# IO-Expander.net
KiCad netlist of a schematic drawn in Altium Designer
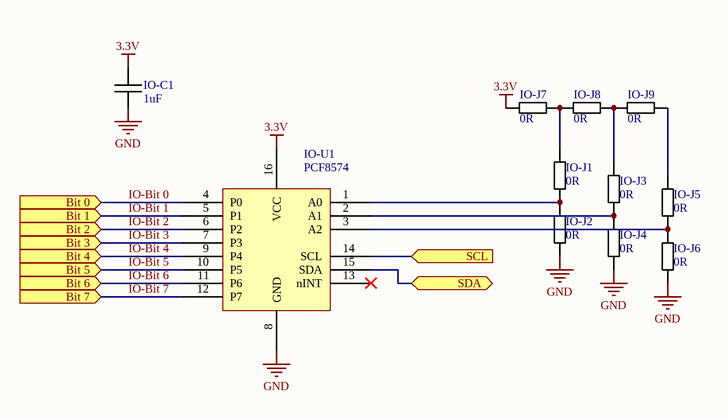
[diagram p0: IO-Expander.SchDoc]

(export (version "E")
  (design (tool "Eeschema 10.0.6"))
  (components
    (comp (ref "IO-C1")
      (value "1uF")
      (footprint "C 0805 / 2012")
      (libsource (lib "Standard") (part "Capacitor"))
    )
    (comp (ref "IO-J1") (value "0R") (footprint "R 0805 / 2012") (libsource (lib "") (part "Resistor_1")))
    (comp (ref "IO-J2") (value "0R") (footprint "R 0805 / 2012") (libsource (lib "") (part "Resistor_1")))
    (comp (ref "IO-J3") (value "0R") (footprint "R 0805 / 2012") (libsource (lib "") (part "Resistor_1")))
    (comp (ref "IO-J4") (value "0R") (footprint "R 0805 / 2012") (libsource (lib "") (part "Resistor_1")))
    (comp (ref "IO-J5") (value "0R") (footprint "R 0805 / 2012") (libsource (lib "") (part "Resistor_1")))
    (comp (ref "IO-J6") (value "0R") (footprint "R 0805 / 2012") (libsource (lib "") (part "Resistor_1")))
    (comp (ref "IO-J7")
      (value "0R")
      (footprint "R 0805 / 2012 wide")
      (libsource (lib "Standard") (part "Resistor"))
    )
    (comp (ref "IO-J8")
      (value "0R")
      (footprint "R 0805 / 2012 wide")
      (libsource (lib "Standard") (part "Resistor"))
    )
    (comp (ref "IO-J9")
      (value "0R")
      (footprint "R 0805 / 2012 wide")
      (libsource (lib "Standard") (part "Resistor"))
    )
    (comp (ref "IO-U1")
      (value "PCF8574")
      (footprint "SOIC-16W")
      (description "8-Bit I/O-Expander")
      (libsource (lib "ICs") (part "PCF8574"))
    )
  )
  (nets
    (net (code "1") (name "/IO-Bit 0") (class "Default")
      (node (ref "IO-U1") (pin "4") (pinfunction "P0_4") (pintype "passive"))
    )
    (net (code "2") (name "/IO-Bit 1") (class "Default")
      (node (ref "IO-U1") (pin "5") (pinfunction "P1_5") (pintype "passive"))
    )
    (net (code "3") (name "/IO-Bit 2") (class "Default")
      (node (ref "IO-U1") (pin "6") (pinfunction "P2_6") (pintype "passive"))
    )
    (net (code "4") (name "/IO-Bit 3") (class "Default")
      (node (ref "IO-U1") (pin "7") (pinfunction "P3_7") (pintype "passive"))
    )
    (net (code "5") (name "/IO-Bit 4") (class "Default")
      (node (ref "IO-U1") (pin "9") (pinfunction "P4_9") (pintype "passive"))
    )
    (net (code "6") (name "/IO-Bit 5") (class "Default")
      (node (ref "IO-U1") (pin "10") (pinfunction "P5_10") (pintype "passive"))
    )
    (net (code "7") (name "/IO-Bit 6") (class "Default")
      (node (ref "IO-U1") (pin "11") (pinfunction "P6_11") (pintype "passive"))
    )
    (net (code "8") (name "/IO-Bit 7") (class "Default")
      (node (ref "IO-U1") (pin "12") (pinfunction "P7_12") (pintype "passive"))
    )
    (net (code "9") (name "/SCL") (class "Default")
      (node (ref "IO-U1") (pin "14") (pinfunction "SCL_14") (pintype "passive"))
    )
    (net (code "10") (name "/SDA") (class "Default")
      (node (ref "IO-U1") (pin "15") (pinfunction "SDA_15") (pintype "passive"))
    )
    (net (code "11") (name "3.3V") (class "Default")
      (node (ref "IO-C1") (pin "1") (pinfunction "1_1") (pintype "passive"))
      (node (ref "IO-J7") (pin "2") (pinfunction "2_2") (pintype "passive"))
      (node (ref "IO-U1") (pin "16") (pinfunction "VCC_16") (pintype "passive"))
    )
    (net (code "12") (name "GND") (class "Default")
      (node (ref "IO-C1") (pin "2") (pinfunction "1_2") (pintype "passive"))
      (node (ref "IO-J2") (pin "1") (pinfunction "1_1") (pintype "passive"))
      (node (ref "IO-J4") (pin "1") (pinfunction "1_1") (pintype "passive"))
      (node (ref "IO-J6") (pin "1") (pinfunction "1_1") (pintype "passive"))
      (node (ref "IO-U1") (pin "8") (pinfunction "GND_8") (pintype "passive"))
    )
    (net (code "13") (name "Net-(IO-J1-Pad2)") (class "Default")
      (node (ref "IO-J1") (pin "2") (pinfunction "2_2") (pintype "passive"))
      (node (ref "IO-J7") (pin "1") (pinfunction "1_1") (pintype "passive"))
      (node (ref "IO-J8") (pin "2") (pinfunction "2_2") (pintype "passive"))
    )
    (net (code "14") (name "Net-(IO-J3-Pad2)") (class "Default")
      (node (ref "IO-J3") (pin "2") (pinfunction "2_2") (pintype "passive"))
      (node (ref "IO-J8") (pin "1") (pinfunction "1_1") (pintype "passive"))
      (node (ref "IO-J9") (pin "2") (pinfunction "2_2") (pintype "passive"))
    )
    (net (code "15") (name "Net-(IO-J5-Pad2)") (class "Default")
      (node (ref "IO-J5") (pin "2") (pinfunction "2_2") (pintype "passive"))
      (node (ref "IO-J9") (pin "1") (pinfunction "1_1") (pintype "passive"))
    )
    (net (code "16") (name "Net-(IO-U1-A0)") (class "Default")
      (node (ref "IO-J1") (pin "1") (pinfunction "1_1") (pintype "passive"))
      (node (ref "IO-J2") (pin "2") (pinfunction "2_2") (pintype "passive"))
      (node (ref "IO-U1") (pin "1") (pinfunction "A0_1") (pintype "passive"))
    )
    (net (code "17") (name "Net-(IO-U1-A1)") (class "Default")
      (node (ref "IO-J3") (pin "1") (pinfunction "1_1") (pintype "passive"))
      (node (ref "IO-J4") (pin "2") (pinfunction "2_2") (pintype "passive"))
      (node (ref "IO-U1") (pin "2") (pinfunction "A1_2") (pintype "passive"))
    )
    (net (code "18") (name "Net-(IO-U1-A2)") (class "Default")
      (node (ref "IO-J5") (pin "1") (pinfunction "1_1") (pintype "passive"))
      (node (ref "IO-J6") (pin "2") (pinfunction "2_2") (pintype "passive"))
      (node (ref "IO-U1") (pin "3") (pinfunction "A2_3") (pintype "passive"))
    )
    (net (code "19") (name "unconnected-(IO-U1-nINT-Pad13)") (class "Default")
      (node (ref "IO-U1") (pin "13") (pinfunction "nINT_13") (pintype "passive+no_connect"))
    )
  )
)
